# powerboard1_2.net
KiCad netlist of a schematic drawn in EAGLE
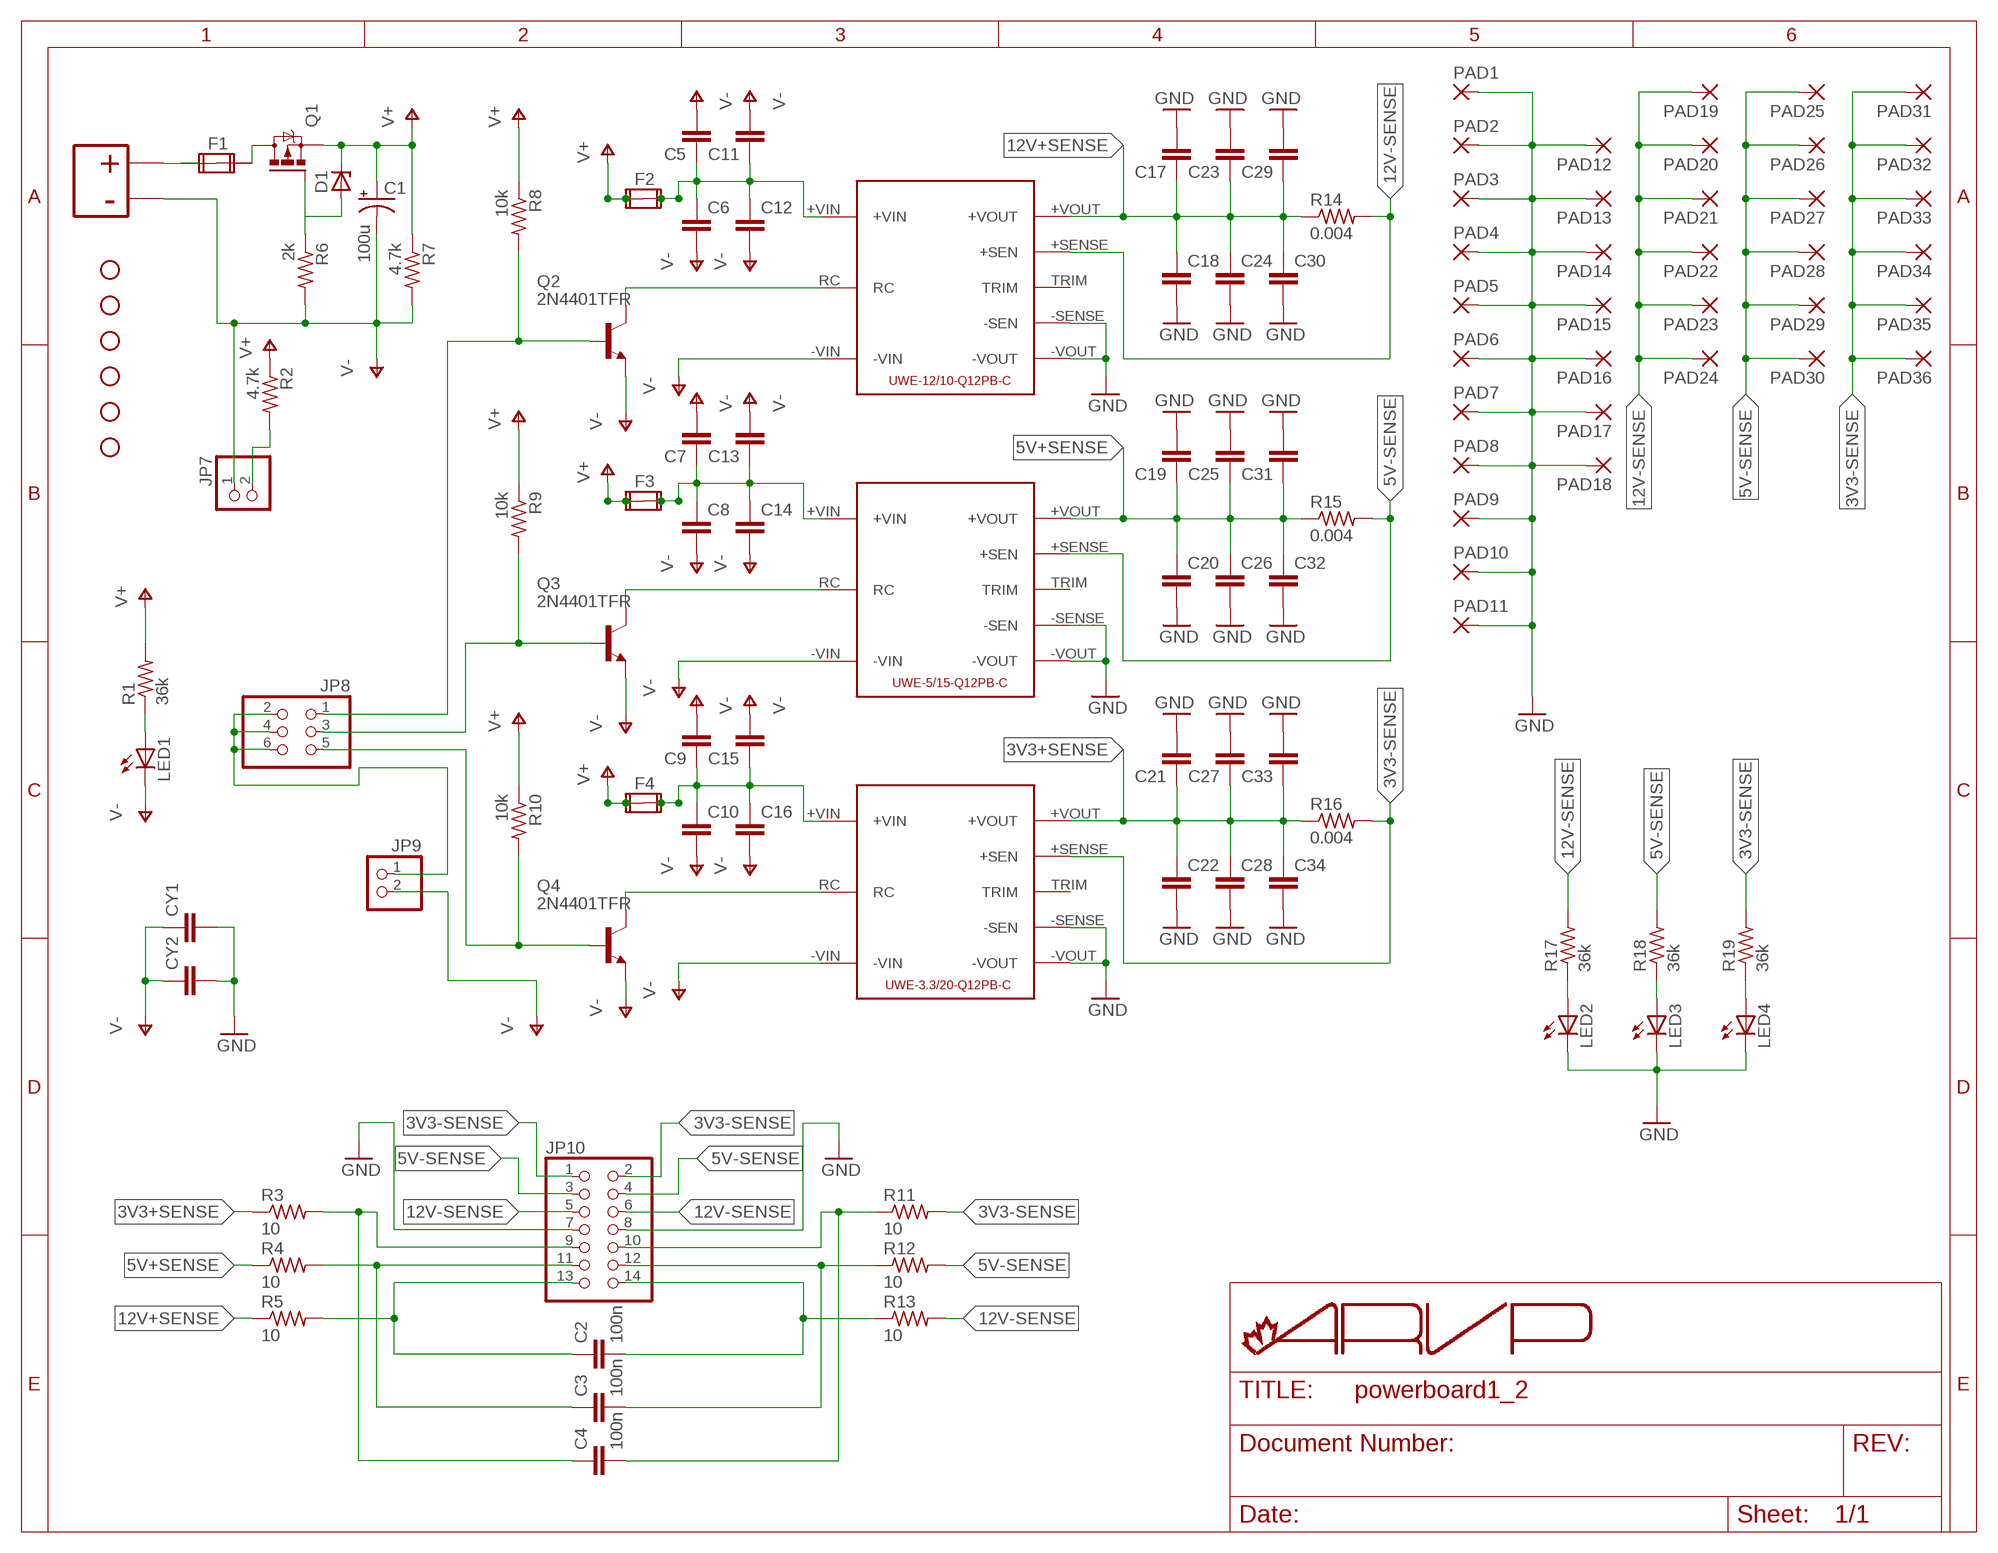
[diagram p0: schematic, sheet 1]

(export (version "E")
  (design (tool "Eeschema 10.0.6"))
  (components
    (comp (ref "C1")
      (value "100u")
      (footprint "eagle-import:E3,5-8")
      (libsource (lib "eagle-import") (part "CPOL-USE3.5-8"))
    )
    (comp (ref "C2")
      (value "100n")
      (footprint "eagle-import:C025-024X044")
      (libsource (lib "eagle-import") (part "C-EU025-024X044"))
    )
    (comp (ref "C3")
      (value "100n")
      (footprint "eagle-import:C025-024X044")
      (libsource (lib "eagle-import") (part "C-EU025-024X044"))
    )
    (comp (ref "C4")
      (value "100n")
      (footprint "eagle-import:C025-024X044")
      (libsource (lib "eagle-import") (part "C-EU025-024X044"))
    )
    (comp (ref "C5")
      (value "C-EU050-035X075")
      (footprint "eagle-import:C050-035X075")
      (libsource (lib "eagle-import") (part "C-EU050-035X075"))
    )
    (comp (ref "C6")
      (value "C-EU050-035X075")
      (footprint "eagle-import:C050-035X075")
      (libsource (lib "eagle-import") (part "C-EU050-035X075"))
    )
    (comp (ref "C7")
      (value "C-EU050-035X075")
      (footprint "eagle-import:C050-035X075")
      (libsource (lib "eagle-import") (part "C-EU050-035X075"))
    )
    (comp (ref "C8")
      (value "C-EU050-035X075")
      (footprint "eagle-import:C050-035X075")
      (libsource (lib "eagle-import") (part "C-EU050-035X075"))
    )
    (comp (ref "C9")
      (value "C-EU050-035X075")
      (footprint "eagle-import:C050-035X075")
      (libsource (lib "eagle-import") (part "C-EU050-035X075"))
    )
    (comp (ref "C10")
      (value "C-EU050-035X075")
      (footprint "eagle-import:C050-035X075")
      (libsource (lib "eagle-import") (part "C-EU050-035X075"))
    )
    (comp (ref "C11")
      (value "C-EU050-035X075")
      (footprint "eagle-import:C050-035X075")
      (libsource (lib "eagle-import") (part "C-EU050-035X075"))
    )
    (comp (ref "C12")
      (value "C-EU050-035X075")
      (footprint "eagle-import:C050-035X075")
      (libsource (lib "eagle-import") (part "C-EU050-035X075"))
    )
    (comp (ref "C13")
      (value "C-EU050-035X075")
      (footprint "eagle-import:C050-035X075")
      (libsource (lib "eagle-import") (part "C-EU050-035X075"))
    )
    (comp (ref "C14")
      (value "C-EU050-035X075")
      (footprint "eagle-import:C050-035X075")
      (libsource (lib "eagle-import") (part "C-EU050-035X075"))
    )
    (comp (ref "C15")
      (value "C-EU050-035X075")
      (footprint "eagle-import:C050-035X075")
      (libsource (lib "eagle-import") (part "C-EU050-035X075"))
    )
    (comp (ref "C16")
      (value "C-EU050-035X075")
      (footprint "eagle-import:C050-035X075")
      (libsource (lib "eagle-import") (part "C-EU050-035X075"))
    )
    (comp (ref "C17")
      (value "C-EU025-040X050")
      (footprint "eagle-import:C025-040X050")
      (libsource (lib "eagle-import") (part "C-EU025-040X050"))
    )
    (comp (ref "C18")
      (value "C-EU025-040X050")
      (footprint "eagle-import:C025-040X050")
      (libsource (lib "eagle-import") (part "C-EU025-040X050"))
    )
    (comp (ref "C19")
      (value "C-EU025-040X050")
      (footprint "eagle-import:C025-040X050")
      (libsource (lib "eagle-import") (part "C-EU025-040X050"))
    )
    (comp (ref "C20")
      (value "C-EU025-040X050")
      (footprint "eagle-import:C025-040X050")
      (libsource (lib "eagle-import") (part "C-EU025-040X050"))
    )
    (comp (ref "C21")
      (value "C-EU025-040X050")
      (footprint "eagle-import:C025-040X050")
      (libsource (lib "eagle-import") (part "C-EU025-040X050"))
    )
    (comp (ref "C22")
      (value "C-EU025-040X050")
      (footprint "eagle-import:C025-040X050")
      (libsource (lib "eagle-import") (part "C-EU025-040X050"))
    )
    (comp (ref "C23")
      (value "C-EU025-040X050")
      (footprint "eagle-import:C025-040X050")
      (libsource (lib "eagle-import") (part "C-EU025-040X050"))
    )
    (comp (ref "C24")
      (value "C-EU025-040X050")
      (footprint "eagle-import:C025-040X050")
      (libsource (lib "eagle-import") (part "C-EU025-040X050"))
    )
    (comp (ref "C25")
      (value "C-EU025-040X050")
      (footprint "eagle-import:C025-040X050")
      (libsource (lib "eagle-import") (part "C-EU025-040X050"))
    )
    (comp (ref "C26")
      (value "C-EU025-040X050")
      (footprint "eagle-import:C025-040X050")
      (libsource (lib "eagle-import") (part "C-EU025-040X050"))
    )
    (comp (ref "C27")
      (value "C-EU025-040X050")
      (footprint "eagle-import:C025-040X050")
      (libsource (lib "eagle-import") (part "C-EU025-040X050"))
    )
    (comp (ref "C28")
      (value "C-EU025-040X050")
      (footprint "eagle-import:C025-040X050")
      (libsource (lib "eagle-import") (part "C-EU025-040X050"))
    )
    (comp (ref "C29")
      (value "C-EU025-040X050")
      (footprint "eagle-import:C025-040X050")
      (libsource (lib "eagle-import") (part "C-EU025-040X050"))
    )
    (comp (ref "C30")
      (value "C-EU025-040X050")
      (footprint "eagle-import:C025-040X050")
      (libsource (lib "eagle-import") (part "C-EU025-040X050"))
    )
    (comp (ref "C31")
      (value "C-EU025-040X050")
      (footprint "eagle-import:C025-040X050")
      (libsource (lib "eagle-import") (part "C-EU025-040X050"))
    )
    (comp (ref "C32")
      (value "C-EU025-040X050")
      (footprint "eagle-import:C025-040X050")
      (libsource (lib "eagle-import") (part "C-EU025-040X050"))
    )
    (comp (ref "C33")
      (value "C-EU025-040X050")
      (footprint "eagle-import:C025-040X050")
      (libsource (lib "eagle-import") (part "C-EU025-040X050"))
    )
    (comp (ref "C34")
      (value "C-EU025-040X050")
      (footprint "eagle-import:C025-040X050")
      (libsource (lib "eagle-import") (part "C-EU025-040X050"))
    )
    (comp (ref "CY1")
      (value "CYYC7B5")
      (footprint "eagle-import:YC7B5")
      (libsource (lib "eagle-import") (part "CYYC7B5"))
    )
    (comp (ref "CY2")
      (value "CYYC7B5")
      (footprint "eagle-import:YC7B5")
      (libsource (lib "eagle-import") (part "CYYC7B5"))
    )
    (comp (ref "D1")
      (value "BZV10")
      (footprint "eagle-import:DO34Z7")
      (libsource (lib "eagle-import") (part "BZV10"))
    )
    (comp (ref "F1")
      (value "FUSE2P")
      (footprint "eagle-import:FUSE1")
      (libsource (lib "eagle-import") (part "FUSE2P"))
    )
    (comp (ref "F2")
      (value "FUSE2P")
      (footprint "eagle-import:FUSE1")
      (libsource (lib "eagle-import") (part "FUSE2P"))
    )
    (comp (ref "F3")
      (value "FUSE2P")
      (footprint "eagle-import:FUSE1")
      (libsource (lib "eagle-import") (part "FUSE2P"))
    )
    (comp (ref "F4")
      (value "FUSE2P")
      (footprint "eagle-import:FUSE1")
      (libsource (lib "eagle-import") (part "FUSE2P"))
    )
    (comp (ref "JP1")
      (value "STAND-OFF")
      (footprint "eagle-import:STAND-OFF")
      (libsource (lib "eagle-import") (part "STAND-OFF"))
    )
    (comp (ref "JP2")
      (value "STAND-OFF")
      (footprint "eagle-import:STAND-OFF")
      (libsource (lib "eagle-import") (part "STAND-OFF"))
    )
    (comp (ref "JP3")
      (value "STAND-OFF")
      (footprint "eagle-import:STAND-OFF")
      (libsource (lib "eagle-import") (part "STAND-OFF"))
    )
    (comp (ref "JP4")
      (value "STAND-OFF")
      (footprint "eagle-import:STAND-OFF")
      (libsource (lib "eagle-import") (part "STAND-OFF"))
    )
    (comp (ref "JP5")
      (value "STAND-OFF")
      (footprint "eagle-import:STAND-OFF")
      (libsource (lib "eagle-import") (part "STAND-OFF"))
    )
    (comp (ref "JP6")
      (value "STAND-OFF")
      (footprint "eagle-import:STAND-OFF")
      (libsource (lib "eagle-import") (part "STAND-OFF"))
    )
    (comp (ref "JP7")
      (value "PINHD-1X2/90")
      (footprint "eagle-import:1X02_90")
      (libsource (lib "eagle-import") (part "PINHD-1X2/90"))
    )
    (comp (ref "JP8")
      (value "PINHD-2X3/90")
      (footprint "eagle-import:2X03_90")
      (libsource (lib "eagle-import") (part "PINHD-2X3/90"))
    )
    (comp (ref "JP9")
      (value "PINHD-1X2/90")
      (footprint "eagle-import:1X02_90")
      (libsource (lib "eagle-import") (part "PINHD-1X2/90"))
    )
    (comp (ref "JP10")
      (value "PINHD-2X7")
      (footprint "eagle-import:2X07")
      (libsource (lib "eagle-import") (part "PINHD-2X7"))
    )
    (comp (ref "LED1")
      (value "LED3MM")
      (footprint "eagle-import:LED3MM")
      (libsource (lib "eagle-import") (part "LED3MM"))
    )
    (comp (ref "LED2")
      (value "LED3MM")
      (footprint "eagle-import:LED3MM")
      (libsource (lib "eagle-import") (part "LED3MM"))
    )
    (comp (ref "LED3")
      (value "LED3MM")
      (footprint "eagle-import:LED3MM")
      (libsource (lib "eagle-import") (part "LED3MM"))
    )
    (comp (ref "LED4")
      (value "LED3MM")
      (footprint "eagle-import:LED3MM")
      (libsource (lib "eagle-import") (part "LED3MM"))
    )
    (comp (ref "PAD1")
      (value "WIREPAD3,17/1,3")
      (footprint "eagle-import:3,17_1,3")
      (libsource (lib "eagle-import") (part "WIREPAD3,17/1,3"))
    )
    (comp (ref "PAD2")
      (value "WIREPAD3,17/1,3")
      (footprint "eagle-import:3,17_1,3")
      (libsource (lib "eagle-import") (part "WIREPAD3,17/1,3"))
    )
    (comp (ref "PAD3")
      (value "WIREPAD3,17/1,3")
      (footprint "eagle-import:3,17_1,3")
      (libsource (lib "eagle-import") (part "WIREPAD3,17/1,3"))
    )
    (comp (ref "PAD4")
      (value "WIREPAD3,17/1,3")
      (footprint "eagle-import:3,17_1,3")
      (libsource (lib "eagle-import") (part "WIREPAD3,17/1,3"))
    )
    (comp (ref "PAD5")
      (value "WIREPAD3,17/1,3")
      (footprint "eagle-import:3,17_1,3")
      (libsource (lib "eagle-import") (part "WIREPAD3,17/1,3"))
    )
    (comp (ref "PAD6")
      (value "WIREPAD3,17/1,3")
      (footprint "eagle-import:3,17_1,3")
      (libsource (lib "eagle-import") (part "WIREPAD3,17/1,3"))
    )
    (comp (ref "PAD7")
      (value "WIREPAD3,17/1,3")
      (footprint "eagle-import:3,17_1,3")
      (libsource (lib "eagle-import") (part "WIREPAD3,17/1,3"))
    )
    (comp (ref "PAD8")
      (value "WIREPAD3,17/1,3")
      (footprint "eagle-import:3,17_1,3")
      (libsource (lib "eagle-import") (part "WIREPAD3,17/1,3"))
    )
    (comp (ref "PAD9")
      (value "WIREPAD3,17/1,3")
      (footprint "eagle-import:3,17_1,3")
      (libsource (lib "eagle-import") (part "WIREPAD3,17/1,3"))
    )
    (comp (ref "PAD10")
      (value "WIREPAD3,17/1,3")
      (footprint "eagle-import:3,17_1,3")
      (libsource (lib "eagle-import") (part "WIREPAD3,17/1,3"))
    )
    (comp (ref "PAD11")
      (value "WIREPAD3,17/1,3")
      (footprint "eagle-import:3,17_1,3")
      (libsource (lib "eagle-import") (part "WIREPAD3,17/1,3"))
    )
    (comp (ref "PAD12")
      (value "WIREPAD3,17/1,3")
      (footprint "eagle-import:3,17_1,3")
      (libsource (lib "eagle-import") (part "WIREPAD3,17/1,3"))
    )
    (comp (ref "PAD13")
      (value "WIREPAD3,17/1,3")
      (footprint "eagle-import:3,17_1,3")
      (libsource (lib "eagle-import") (part "WIREPAD3,17/1,3"))
    )
    (comp (ref "PAD14")
      (value "WIREPAD3,17/1,3")
      (footprint "eagle-import:3,17_1,3")
      (libsource (lib "eagle-import") (part "WIREPAD3,17/1,3"))
    )
    (comp (ref "PAD15")
      (value "WIREPAD3,17/1,3")
      (footprint "eagle-import:3,17_1,3")
      (libsource (lib "eagle-import") (part "WIREPAD3,17/1,3"))
    )
    (comp (ref "PAD16")
      (value "WIREPAD3,17/1,3")
      (footprint "eagle-import:3,17_1,3")
      (libsource (lib "eagle-import") (part "WIREPAD3,17/1,3"))
    )
    (comp (ref "PAD17")
      (value "WIREPAD3,17/1,3")
      (footprint "eagle-import:3,17_1,3")
      (libsource (lib "eagle-import") (part "WIREPAD3,17/1,3"))
    )
    (comp (ref "PAD18")
      (value "WIREPAD3,17/1,3")
      (footprint "eagle-import:3,17_1,3")
      (libsource (lib "eagle-import") (part "WIREPAD3,17/1,3"))
    )
    (comp (ref "PAD19")
      (value "WIREPAD3,17/1,3")
      (footprint "eagle-import:3,17_1,3")
      (libsource (lib "eagle-import") (part "WIREPAD3,17/1,3"))
    )
    (comp (ref "PAD20")
      (value "WIREPAD3,17/1,3")
      (footprint "eagle-import:3,17_1,3")
      (libsource (lib "eagle-import") (part "WIREPAD3,17/1,3"))
    )
    (comp (ref "PAD21")
      (value "WIREPAD3,17/1,3")
      (footprint "eagle-import:3,17_1,3")
      (libsource (lib "eagle-import") (part "WIREPAD3,17/1,3"))
    )
    (comp (ref "PAD22")
      (value "WIREPAD3,17/1,3")
      (footprint "eagle-import:3,17_1,3")
      (libsource (lib "eagle-import") (part "WIREPAD3,17/1,3"))
    )
    (comp (ref "PAD23")
      (value "WIREPAD3,17/1,3")
      (footprint "eagle-import:3,17_1,3")
      (libsource (lib "eagle-import") (part "WIREPAD3,17/1,3"))
    )
    (comp (ref "PAD24")
      (value "WIREPAD3,17/1,3")
      (footprint "eagle-import:3,17_1,3")
      (libsource (lib "eagle-import") (part "WIREPAD3,17/1,3"))
    )
    (comp (ref "PAD25")
      (value "WIREPAD3,17/1,3")
      (footprint "eagle-import:3,17_1,3")
      (libsource (lib "eagle-import") (part "WIREPAD3,17/1,3"))
    )
    (comp (ref "PAD26")
      (value "WIREPAD3,17/1,3")
      (footprint "eagle-import:3,17_1,3")
      (libsource (lib "eagle-import") (part "WIREPAD3,17/1,3"))
    )
    (comp (ref "PAD27")
      (value "WIREPAD3,17/1,3")
      (footprint "eagle-import:3,17_1,3")
      (libsource (lib "eagle-import") (part "WIREPAD3,17/1,3"))
    )
    (comp (ref "PAD28")
      (value "WIREPAD3,17/1,3")
      (footprint "eagle-import:3,17_1,3")
      (libsource (lib "eagle-import") (part "WIREPAD3,17/1,3"))
    )
    (comp (ref "PAD29")
      (value "WIREPAD3,17/1,3")
      (footprint "eagle-import:3,17_1,3")
      (libsource (lib "eagle-import") (part "WIREPAD3,17/1,3"))
    )
    (comp (ref "PAD30")
      (value "WIREPAD3,17/1,3")
      (footprint "eagle-import:3,17_1,3")
      (libsource (lib "eagle-import") (part "WIREPAD3,17/1,3"))
    )
    (comp (ref "PAD31")
      (value "WIREPAD3,17/1,3")
      (footprint "eagle-import:3,17_1,3")
      (libsource (lib "eagle-import") (part "WIREPAD3,17/1,3"))
    )
    (comp (ref "PAD32")
      (value "WIREPAD3,17/1,3")
      (footprint "eagle-import:3,17_1,3")
      (libsource (lib "eagle-import") (part "WIREPAD3,17/1,3"))
    )
    (comp (ref "PAD33")
      (value "WIREPAD3,17/1,3")
      (footprint "eagle-import:3,17_1,3")
      (libsource (lib "eagle-import") (part "WIREPAD3,17/1,3"))
    )
    (comp (ref "PAD34")
      (value "WIREPAD3,17/1,3")
      (footprint "eagle-import:3,17_1,3")
      (libsource (lib "eagle-import") (part "WIREPAD3,17/1,3"))
    )
    (comp (ref "PAD35")
      (value "WIREPAD3,17/1,3")
      (footprint "eagle-import:3,17_1,3")
      (libsource (lib "eagle-import") (part "WIREPAD3,17/1,3"))
    )
    (comp (ref "PAD36")
      (value "WIREPAD3,17/1,3")
      (footprint "eagle-import:3,17_1,3")
      (libsource (lib "eagle-import") (part "WIREPAD3,17/1,3"))
    )
    (comp (ref "Q1")
      (value "IPP80P03P4L04AKSA1")
      (footprint "eagle-import:TO220BV")
      (libsource (lib "eagle-import") (part "IPP80P03P4L04AKSA1"))
    )
    (comp (ref "Q2")
      (value "2N4401TFR")
      (footprint "eagle-import:TO92-EBC")
      (libsource (lib "eagle-import") (part "2N4401TFR"))
    )
    (comp (ref "Q3")
      (value "2N4401TFR")
      (footprint "eagle-import:TO92-EBC")
      (libsource (lib "eagle-import") (part "2N4401TFR"))
    )
    (comp (ref "Q4")
      (value "2N4401TFR")
      (footprint "eagle-import:TO92-EBC")
      (libsource (lib "eagle-import") (part "2N4401TFR"))
    )
    (comp (ref "R1")
      (value "36k")
      (footprint "eagle-import:0204_7")
      (libsource (lib "eagle-import") (part "resistor_R-US_0204/7"))
    )
    (comp (ref "R2")
      (value "4.7k")
      (footprint "eagle-import:0204_7")
      (libsource (lib "eagle-import") (part "resistor_R-US_0204/7"))
    )
    (comp (ref "R3")
      (value "10")
      (footprint "eagle-import:0204_5")
      (libsource (lib "eagle-import") (part "R-US_0204/5"))
    )
    (comp (ref "R4")
      (value "10")
      (footprint "eagle-import:0204_5")
      (libsource (lib "eagle-import") (part "R-US_0204/5"))
    )
    (comp (ref "R5")
      (value "10")
      (footprint "eagle-import:0204_5")
      (libsource (lib "eagle-import") (part "R-US_0204/5"))
    )
    (comp (ref "R6")
      (value "2k")
      (footprint "eagle-import:0204_7")
      (libsource (lib "eagle-import") (part "resistor_R-US_0204/7"))
    )
    (comp (ref "R7")
      (value "4.7k")
      (footprint "eagle-import:0204_7")
      (libsource (lib "eagle-import") (part "resistor_R-US_0204/7"))
    )
    (comp (ref "R8")
      (value "10k")
      (footprint "eagle-import:0204_7")
      (libsource (lib "eagle-import") (part "resistor_R-US_0204/7"))
    )
    (comp (ref "R9")
      (value "10k")
      (footprint "eagle-import:0204_7")
      (libsource (lib "eagle-import") (part "resistor_R-US_0204/7"))
    )
    (comp (ref "R10")
      (value "10k")
      (footprint "eagle-import:0204_7")
      (libsource (lib "eagle-import") (part "resistor_R-US_0204/7"))
    )
    (comp (ref "R11")
      (value "10")
      (footprint "eagle-import:0204_5")
      (libsource (lib "eagle-import") (part "R-US_0204/5"))
    )
    (comp (ref "R12")
      (value "10")
      (footprint "eagle-import:0204_5")
      (libsource (lib "eagle-import") (part "R-US_0204/5"))
    )
    (comp (ref "R13")
      (value "10")
      (footprint "eagle-import:0204_5")
      (libsource (lib "eagle-import") (part "R-US_0204/5"))
    )
    (comp (ref "R14")
      (value "0.004")
      (footprint "eagle-import:0617_22")
      (libsource (lib "eagle-import") (part "R-US_0617/22"))
    )
    (comp (ref "R15")
      (value "0.004")
      (footprint "eagle-import:0617_22")
      (libsource (lib "eagle-import") (part "R-US_0617/22"))
    )
    (comp (ref "R16")
      (value "0.004")
      (footprint "eagle-import:0617_22")
      (libsource (lib "eagle-import") (part "R-US_0617/22"))
    )
    (comp (ref "R17")
      (value "36k")
      (footprint "eagle-import:0204_7")
      (libsource (lib "eagle-import") (part "resistor_R-US_0204/7"))
    )
    (comp (ref "R18")
      (value "36k")
      (footprint "eagle-import:0204_7")
      (libsource (lib "eagle-import") (part "resistor_R-US_0204/7"))
    )
    (comp (ref "R19")
      (value "36k")
      (footprint "eagle-import:0204_7")
      (libsource (lib "eagle-import") (part "resistor_R-US_0204/7"))
    )
    (comp (ref "T1")
      (value "2_POS_TERMINAL")
      (footprint "eagle-import:PHOENIX_CONTACT_MKDS_5_2-7.62")
      (libsource (lib "eagle-import") (part "2_POS_TERMINAL"))
    )
    (comp (ref "U1")
      (value "UWE-12/10-Q12PB-C")
      (footprint "eagle-import:UWE-100-120W")
      (libsource (lib "eagle-import") (part "UWE-12/10-Q12PB-C"))
    )
    (comp (ref "U2")
      (value "UWE-5/15-Q12PB-C")
      (footprint "eagle-import:UWE-100-120W")
      (libsource (lib "eagle-import") (part "UWE-5/15-Q12PB-C"))
    )
    (comp (ref "U3")
      (value "UWE-3.3/20-Q12PB-C")
      (footprint "eagle-import:UWE-100-120W")
      (libsource (lib "eagle-import") (part "UWE-3.3/20-Q12PB-C"))
    )
  )
  (nets
    (net (code "1") (name "3V3+SENSE") (class "Default")
      (node (ref "C21") (pin "1") (pinfunction "1_1") (pintype "passive"))
      (node (ref "C22") (pin "1") (pinfunction "1_1") (pintype "passive"))
      (node (ref "C27") (pin "1") (pinfunction "1_1") (pintype "passive"))
      (node (ref "C28") (pin "1") (pinfunction "1_1") (pintype "passive"))
      (node (ref "C33") (pin "1") (pinfunction "1_1") (pintype "passive"))
      (node (ref "C34") (pin "1") (pinfunction "1_1") (pintype "passive"))
      (node (ref "R16") (pin "1") (pinfunction "1_1") (pintype "passive"))
      (node (ref "R3") (pin "1") (pinfunction "1_1") (pintype "passive"))
      (node (ref "U3") (pin "+VOUT") (pinfunction "+VOUT_+VOUT") (pintype "power_in"))
    )
    (net (code "2") (name "3V3-SENSE") (class "Default")
      (node (ref "JP10") (pin "1") (pinfunction "1_1") (pintype "passive"))
      (node (ref "JP10") (pin "2") (pinfunction "2_2") (pintype "passive"))
      (node (ref "PAD31") (pin "1") (pinfunction "P_1") (pintype "passive"))
      (node (ref "PAD32") (pin "1") (pinfunction "P_1") (pintype "passive"))
      (node (ref "PAD33") (pin "1") (pinfunction "P_1") (pintype "passive"))
      (node (ref "PAD34") (pin "1") (pinfunction "P_1") (pintype "passive"))
      (node (ref "PAD35") (pin "1") (pinfunction "P_1") (pintype "passive"))
      (node (ref "PAD36") (pin "1") (pinfunction "P_1") (pintype "passive"))
      (node (ref "R11") (pin "2") (pinfunction "2_2") (pintype "passive"))
      (node (ref "R16") (pin "2") (pinfunction "2_2") (pintype "passive"))
      (node (ref "R19") (pin "2") (pinfunction "2_2") (pintype "passive"))
      (node (ref "U3") (pin "+SENSE") (pinfunction "+SEN_+SENSE") (pintype "bidirectional"))
    )
    (net (code "3") (name "5V+SENSE") (class "Default")
      (node (ref "C19") (pin "1") (pinfunction "1_1") (pintype "passive"))
      (node (ref "C20") (pin "1") (pinfunction "1_1") (pintype "passive"))
      (node (ref "C25") (pin "1") (pinfunction "1_1") (pintype "passive"))
      (node (ref "C26") (pin "1") (pinfunction "1_1") (pintype "passive"))
      (node (ref "C31") (pin "1") (pinfunction "1_1") (pintype "passive"))
      (node (ref "C32") (pin "1") (pinfunction "1_1") (pintype "passive"))
      (node (ref "R15") (pin "1") (pinfunction "1_1") (pintype "passive"))
      (node (ref "R4") (pin "1") (pinfunction "1_1") (pintype "passive"))
      (node (ref "U2") (pin "+VOUT") (pinfunction "+VOUT_+VOUT") (pintype "power_in"))
    )
    (net (code "4") (name "5V-SENSE") (class "Default")
      (node (ref "JP10") (pin "3") (pinfunction "3_3") (pintype "passive"))
      (node (ref "JP10") (pin "4") (pinfunction "4_4") (pintype "passive"))
      (node (ref "PAD25") (pin "1") (pinfunction "P_1") (pintype "passive"))
      (node (ref "PAD26") (pin "1") (pinfunction "P_1") (pintype "passive"))
      (node (ref "PAD27") (pin "1") (pinfunction "P_1") (pintype "passive"))
      (node (ref "PAD28") (pin "1") (pinfunction "P_1") (pintype "passive"))
      (node (ref "PAD29") (pin "1") (pinfunction "P_1") (pintype "passive"))
      (node (ref "PAD30") (pin "1") (pinfunction "P_1") (pintype "passive"))
      (node (ref "R12") (pin "2") (pinfunction "2_2") (pintype "passive"))
      (node (ref "R15") (pin "2") (pinfunction "2_2") (pintype "passive"))
      (node (ref "R18") (pin "2") (pinfunction "2_2") (pintype "passive"))
      (node (ref "U2") (pin "+SENSE") (pinfunction "+SEN_+SENSE") (pintype "bidirectional"))
    )
    (net (code "5") (name "12V+SENSE") (class "Default")
      (node (ref "C17") (pin "1") (pinfunction "1_1") (pintype "passive"))
      (node (ref "C18") (pin "1") (pinfunction "1_1") (pintype "passive"))
      (node (ref "C23") (pin "1") (pinfunction "1_1") (pintype "passive"))
      (node (ref "C24") (pin "1") (pinfunction "1_1") (pintype "passive"))
      (node (ref "C29") (pin "1") (pinfunction "1_1") (pintype "passive"))
      (node (ref "C30") (pin "1") (pinfunction "1_1") (pintype "passive"))
      (node (ref "R14") (pin "1") (pinfunction "1_1") (pintype "passive"))
      (node (ref "R5") (pin "1") (pinfunction "1_1") (pintype "passive"))
      (node (ref "U1") (pin "+VOUT") (pinfunction "+VOUT_+VOUT") (pintype "power_in"))
    )
    (net (code "6") (name "12V-SENSE") (class "Default")
      (node (ref "JP10") (pin "5") (pinfunction "5_5") (pintype "passive"))
      (node (ref "JP10") (pin "6") (pinfunction "6_6") (pintype "passive"))
      (node (ref "PAD19") (pin "1") (pinfunction "P_1") (pintype "passive"))
      (node (ref "PAD20") (pin "1") (pinfunction "P_1") (pintype "passive"))
      (node (ref "PAD21") (pin "1") (pinfunction "P_1") (pintype "passive"))
      (node (ref "PAD22") (pin "1") (pinfunction "P_1") (pintype "passive"))
      (node (ref "PAD23") (pin "1") (pinfunction "P_1") (pintype "passive"))
      (node (ref "PAD24") (pin "1") (pinfunction "P_1") (pintype "passive"))
      (node (ref "R13") (pin "2") (pinfunction "2_2") (pintype "passive"))
      (node (ref "R14") (pin "2") (pinfunction "2_2") (pintype "passive"))
      (node (ref "R17") (pin "2") (pinfunction "2_2") (pintype "passive"))
      (node (ref "U1") (pin "+SENSE") (pinfunction "+SEN_+SENSE") (pintype "bidirectional"))
    )
    (net (code "7") (name "GND") (class "Default")
      (node (ref "C17") (pin "2") (pinfunction "2_2") (pintype "passive"))
      (node (ref "C18") (pin "2") (pinfunction "2_2") (pintype "passive"))
      (node (ref "C19") (pin "2") (pinfunction "2_2") (pintype "passive"))
      (node (ref "C20") (pin "2") (pinfunction "2_2") (pintype "passive"))
      (node (ref "C21") (pin "2") (pinfunction "2_2") (pintype "passive"))
      (node (ref "C22") (pin "2") (pinfunction "2_2") (pintype "passive"))
      (node (ref "C23") (pin "2") (pinfunction "2_2") (pintype "passive"))
      (node (ref "C24") (pin "2") (pinfunction "2_2") (pintype "passive"))
      (node (ref "C25") (pin "2") (pinfunction "2_2") (pintype "passive"))
      (node (ref "C26") (pin "2") (pinfunction "2_2") (pintype "passive"))
      (node (ref "C27") (pin "2") (pinfunction "2_2") (pintype "passive"))
      (node (ref "C28") (pin "2") (pinfunction "2_2") (pintype "passive"))
      (node (ref "C29") (pin "2") (pinfunction "2_2") (pintype "passive"))
      (node (ref "C30") (pin "2") (pinfunction "2_2") (pintype "passive"))
      (node (ref "C31") (pin "2") (pinfunction "2_2") (pintype "passive"))
      (node (ref "C32") (pin "2") (pinfunction "2_2") (pintype "passive"))
      (node (ref "C33") (pin "2") (pinfunction "2_2") (pintype "passive"))
      (node (ref "C34") (pin "2") (pinfunction "2_2") (pintype "passive"))
      (node (ref "CY1") (pin "2") (pinfunction "2_2") (pintype "passive"))
      (node (ref "CY2") (pin "2") (pinfunction "2_2") (pintype "passive"))
      (node (ref "JP10") (pin "7") (pinfunction "7_7") (pintype "passive"))
      (node (ref "JP10") (pin "8") (pinfunction "8_8") (pintype "passive"))
      (node (ref "LED2") (pin "K") (pinfunction "C_K") (pintype "passive"))
      (node (ref "LED3") (pin "K") (pinfunction "C_K") (pintype "passive"))
      (node (ref "LED4") (pin "K") (pinfunction "C_K") (pintype "passive"))
      (node (ref "PAD1") (pin "1") (pinfunction "P_1") (pintype "passive"))
      (node (ref "PAD10") (pin "1") (pinfunction "P_1") (pintype "passive"))
      (node (ref "PAD11") (pin "1") (pinfunction "P_1") (pintype "passive"))
      (node (ref "PAD12") (pin "1") (pinfunction "P_1") (pintype "passive"))
      (node (ref "PAD13") (pin "1") (pinfunction "P_1") (pintype "passive"))
      (node (ref "PAD14") (pin "1") (pinfunction "P_1") (pintype "passive"))
      (node (ref "PAD15") (pin "1") (pinfunction "P_1") (pintype "passive"))
      (node (ref "PAD16") (pin "1") (pinfunction "P_1") (pintype "passive"))
      (node (ref "PAD17") (pin "1") (pinfunction "P_1") (pintype "passive"))
      (node (ref "PAD18") (pin "1") (pinfunction "P_1") (pintype "passive"))
      (node (ref "PAD2") (pin "1") (pinfunction "P_1") (pintype "passive"))
      (node (ref "PAD3") (pin "1") (pinfunction "P_1") (pintype "passive"))
      (node (ref "PAD4") (pin "1") (pinfunction "P_1") (pintype "passive"))
      (node (ref "PAD5") (pin "1") (pinfunction "P_1") (pintype "passive"))
      (node (ref "PAD6") (pin "1") (pinfunction "P_1") (pintype "passive"))
      (node (ref "PAD7") (pin "1") (pinfunction "P_1") (pintype "passive"))
      (node (ref "PAD8") (pin "1") (pinfunction "P_1") (pintype "passive"))
      (node (ref "PAD9") (pin "1") (pinfunction "P_1") (pintype "passive"))
      (node (ref "U1") (pin "-SENSE") (pinfunction "-SEN_-SENSE") (pintype "bidirectional"))
      (node (ref "U1") (pin "-VOUT") (pinfunction "-VOUT_-VOUT") (pintype "power_in"))
      (node (ref "U2") (pin "-SENSE") (pinfunction "-SEN_-SENSE") (pintype "bidirectional"))
      (node (ref "U2") (pin "-VOUT") (pinfunction "-VOUT_-VOUT") (pintype "power_in"))
      (node (ref "U3") (pin "-SENSE") (pinfunction "-SEN_-SENSE") (pintype "bidirectional"))
      (node (ref "U3") (pin "-VOUT") (pinfunction "-VOUT_-VOUT") (pintype "power_in"))
    )
    (net (code "8") (name "Net-(C2-Pad1)") (class "Default")
      (node (ref "C2") (pin "1") (pinfunction "1_1") (pintype "passive"))
      (node (ref "JP10") (pin "13") (pinfunction "13_13") (pintype "passive"))
      (node (ref "R5") (pin "2") (pinfunction "2_2") (pintype "passive"))
    )
    (net (code "9") (name "Net-(C2-Pad2)") (class "Default")
      (node (ref "C2") (pin "2") (pinfunction "2_2") (pintype "passive"))
      (node (ref "JP10") (pin "14") (pinfunction "14_14") (pintype "passive"))
      (node (ref "R13") (pin "1") (pinfunction "1_1") (pintype "passive"))
    )
    (net (code "10") (name "Net-(C3-Pad1)") (class "Default")
      (node (ref "C3") (pin "1") (pinfunction "1_1") (pintype "passive"))
      (node (ref "JP10") (pin "11") (pinfunction "11_11") (pintype "passive"))
      (node (ref "R4") (pin "2") (pinfunction "2_2") (pintype "passive"))
    )
    (net (code "11") (name "Net-(C3-Pad2)") (class "Default")
      (node (ref "C3") (pin "2") (pinfunction "2_2") (pintype "passive"))
      (node (ref "JP10") (pin "12") (pinfunction "12_12") (pintype "passive"))
      (node (ref "R12") (pin "1") (pinfunction "1_1") (pintype "passive"))
    )
    (net (code "12") (name "Net-(C4-Pad1)") (class "Default")
      (node (ref "C4") (pin "1") (pinfunction "1_1") (pintype "passive"))
      (node (ref "JP10") (pin "9") (pinfunction "9_9") (pintype "passive"))
      (node (ref "R3") (pin "2") (pinfunction "2_2") (pintype "passive"))
    )
    (net (code "13") (name "Net-(C4-Pad2)") (class "Default")
      (node (ref "C4") (pin "2") (pinfunction "2_2") (pintype "passive"))
      (node (ref "JP10") (pin "10") (pinfunction "10_10") (pintype "passive"))
      (node (ref "R11") (pin "1") (pinfunction "1_1") (pintype "passive"))
    )
    (net (code "14") (name "Net-(C10-Pad1)") (class "Default")
      (node (ref "C10") (pin "1") (pinfunction "1_1") (pintype "passive"))
      (node (ref "C15") (pin "1") (pinfunction "1_1") (pintype "passive"))
      (node (ref "C16") (pin "1") (pinfunction "1_1") (pintype "passive"))
      (node (ref "C9") (pin "1") (pinfunction "1_1") (pintype "passive"))
      (node (ref "F4") (pin "2A") (pinfunction "2A_2A") (pintype "passive"))
      (node (ref "F4") (pin "2B") (pinfunction "2B_2B") (pintype "passive"))
      (node (ref "U3") (pin "+VIN") (pinfunction "+VIN_+VIN") (pintype "power_in"))
    )
    (net (code "15") (name "Net-(C11-Pad1)") (class "Default")
      (node (ref "C11") (pin "1") (pinfunction "1_1") (pintype "passive"))
      (node (ref "C12") (pin "1") (pinfunction "1_1") (pintype "passive"))
      (node (ref "C5") (pin "1") (pinfunction "1_1") (pintype "passive"))
      (node (ref "C6") (pin "1") (pinfunction "1_1") (pintype "passive"))
      (node (ref "F2") (pin "2A") (pinfunction "2A_2A") (pintype "passive"))
      (node (ref "F2") (pin "2B") (pinfunction "2B_2B") (pintype "passive"))
      (node (ref "U1") (pin "+VIN") (pinfunction "+VIN_+VIN") (pintype "power_in"))
    )
    (net (code "16") (name "Net-(C13-Pad1)") (class "Default")
      (node (ref "C13") (pin "1") (pinfunction "1_1") (pintype "passive"))
      (node (ref "C14") (pin "1") (pinfunction "1_1") (pintype "passive"))
      (node (ref "C7") (pin "1") (pinfunction "1_1") (pintype "passive"))
      (node (ref "C8") (pin "1") (pinfunction "1_1") (pintype "passive"))
      (node (ref "F3") (pin "2A") (pinfunction "2A_2A") (pintype "passive"))
      (node (ref "F3") (pin "2B") (pinfunction "2B_2B") (pintype "passive"))
      (node (ref "U2") (pin "+VIN") (pinfunction "+VIN_+VIN") (pintype "power_in"))
    )
    (net (code "17") (name "Net-(D1-PadA)") (class "Default")
      (node (ref "D1") (pin "A") (pinfunction "A_A") (pintype "passive"))
      (node (ref "Q1") (pin "G") (pinfunction "G_G") (pintype "power_in"))
      (node (ref "R6") (pin "1") (pinfunction "1_1") (pintype "passive"))
    )
    (net (code "18") (name "Net-(F1-Pad1A)") (class "Default")
      (node (ref "F1") (pin "1A") (pinfunction "1A_1A") (pintype "passive"))
      (node (ref "F1") (pin "1B") (pinfunction "1B_1B") (pintype "passive"))
      (node (ref "T1") (pin "P$1") (pinfunction "P$1_P$1") (pintype "power_in"))
    )
    (net (code "19") (name "Net-(F1-Pad2A)") (class "Default")
      (node (ref "F1") (pin "2A") (pinfunction "2A_2A") (pintype "passive"))
      (node (ref "F1") (pin "2B") (pinfunction "2B_2B") (pintype "passive"))
      (node (ref "Q1") (pin "D") (pinfunction "D_D") (pintype "power_in"))
    )
    (net (code "20") (name "Net-(JP7-Pad2)") (class "Default")
      (node (ref "JP7") (pin "2") (pinfunction "2_2") (pintype "passive"))
      (node (ref "R2") (pin "2") (pinfunction "2_2") (pintype "passive"))
    )
    (net (code "21") (name "Net-(JP8-Pad1)") (class "Default")
      (node (ref "JP8") (pin "1") (pinfunction "1_1") (pintype "passive"))
      (node (ref "Q2") (pin "B") (pinfunction "B_B") (pintype "passive"))
      (node (ref "R8") (pin "2") (pinfunction "2_2") (pintype "passive"))
    )
    (net (code "22") (name "Net-(JP8-Pad2)") (class "Default")
      (node (ref "JP8") (pin "2") (pinfunction "2_2") (pintype "passive"))
      (node (ref "JP8") (pin "4") (pinfunction "4_4") (pintype "passive"))
      (node (ref "JP8") (pin "6") (pinfunction "6_6") (pintype "passive"))
      (node (ref "JP9") (pin "1") (pinfunction "1_1") (pintype "passive"))
    )
    (net (code "23") (name "Net-(JP8-Pad3)") (class "Default")
      (node (ref "JP8") (pin "3") (pinfunction "3_3") (pintype "passive"))
      (node (ref "Q3") (pin "B") (pinfunction "B_B") (pintype "passive"))
      (node (ref "R9") (pin "2") (pinfunction "2_2") (pintype "passive"))
    )
    (net (code "24") (name "Net-(JP8-Pad5)") (class "Default")
      (node (ref "JP8") (pin "5") (pinfunction "5_5") (pintype "passive"))
      (node (ref "Q4") (pin "B") (pinfunction "B_B") (pintype "passive"))
      (node (ref "R10") (pin "2") (pinfunction "2_2") (pintype "passive"))
    )
    (net (code "25") (name "Net-(LED1-PadA)") (class "Default")
      (node (ref "LED1") (pin "A") (pinfunction "A_A") (pintype "passive"))
      (node (ref "R1") (pin "1") (pinfunction "1_1") (pintype "passive"))
    )
    (net (code "26") (name "Net-(LED2-PadA)") (class "Default")
      (node (ref "LED2") (pin "A") (pinfunction "A_A") (pintype "passive"))
      (node (ref "R17") (pin "1") (pinfunction "1_1") (pintype "passive"))
    )
    (net (code "27") (name "Net-(LED3-PadA)") (class "Default")
      (node (ref "LED3") (pin "A") (pinfunction "A_A") (pintype "passive"))
      (node (ref "R18") (pin "1") (pinfunction "1_1") (pintype "passive"))
    )
    (net (code "28") (name "Net-(LED4-PadA)") (class "Default")
      (node (ref "LED4") (pin "A") (pinfunction "A_A") (pintype "passive"))
      (node (ref "R19") (pin "1") (pinfunction "1_1") (pintype "passive"))
    )
    (net (code "29") (name "Net-(Q2-PadC)") (class "Default")
      (node (ref "Q2") (pin "C") (pinfunction "C_C") (pintype "passive"))
      (node (ref "U1") (pin "RC") (pinfunction "RC_RC") (pintype "bidirectional"))
    )
    (net (code "30") (name "Net-(Q3-PadC)") (class "Default")
      (node (ref "Q3") (pin "C") (pinfunction "C_C") (pintype "passive"))
      (node (ref "U2") (pin "RC") (pinfunction "RC_RC") (pintype "bidirectional"))
    )
    (net (code "31") (name "Net-(Q4-PadC)") (class "Default")
      (node (ref "Q4") (pin "C") (pinfunction "C_C") (pintype "passive"))
      (node (ref "U3") (pin "RC") (pinfunction "RC_RC") (pintype "bidirectional"))
    )
    (net (code "32") (name "V+") (class "Default")
      (node (ref "C1") (pin "+") (pinfunction "+_+") (pintype "passive"))
      (node (ref "D1") (pin "C") (pinfunction "C_C") (pintype "passive"))
      (node (ref "F2") (pin "1A") (pinfunction "1A_1A") (pintype "passive"))
      (node (ref "F2") (pin "1B") (pinfunction "1B_1B") (pintype "passive"))
      (node (ref "F3") (pin "1A") (pinfunction "1A_1A") (pintype "passive"))
      (node (ref "F3") (pin "1B") (pinfunction "1B_1B") (pintype "passive"))
      (node (ref "F4") (pin "1A") (pinfunction "1A_1A") (pintype "passive"))
      (node (ref "F4") (pin "1B") (pinfunction "1B_1B") (pintype "passive"))
      (node (ref "Q1") (pin "S") (pinfunction "S_S") (pintype "power_in"))
      (node (ref "R1") (pin "2") (pinfunction "2_2") (pintype "passive"))
      (node (ref "R10") (pin "1") (pinfunction "1_1") (pintype "passive"))
      (node (ref "R2") (pin "1") (pinfunction "1_1") (pintype "passive"))
      (node (ref "R7") (pin "1") (pinfunction "1_1") (pintype "passive"))
      (node (ref "R8") (pin "1") (pinfunction "1_1") (pintype "passive"))
      (node (ref "R9") (pin "1") (pinfunction "1_1") (pintype "passive"))
    )
    (net (code "33") (name "V-") (class "Default")
      (node (ref "C1") (pin "-") (pinfunction "-_-") (pintype "passive"))
      (node (ref "C10") (pin "2") (pinfunction "2_2") (pintype "passive"))
      (node (ref "C11") (pin "2") (pinfunction "2_2") (pintype "passive"))
      (node (ref "C12") (pin "2") (pinfunction "2_2") (pintype "passive"))
      (node (ref "C13") (pin "2") (pinfunction "2_2") (pintype "passive"))
      (node (ref "C14") (pin "2") (pinfunction "2_2") (pintype "passive"))
      (node (ref "C15") (pin "2") (pinfunction "2_2") (pintype "passive"))
      (node (ref "C16") (pin "2") (pinfunction "2_2") (pintype "passive"))
      (node (ref "C5") (pin "2") (pinfunction "2_2") (pintype "passive"))
      (node (ref "C6") (pin "2") (pinfunction "2_2") (pintype "passive"))
      (node (ref "C7") (pin "2") (pinfunction "2_2") (pintype "passive"))
      (node (ref "C8") (pin "2") (pinfunction "2_2") (pintype "passive"))
      (node (ref "C9") (pin "2") (pinfunction "2_2") (pintype "passive"))
      (node (ref "CY1") (pin "1") (pinfunction "1_1") (pintype "passive"))
      (node (ref "CY2") (pin "1") (pinfunction "1_1") (pintype "passive"))
      (node (ref "JP7") (pin "1") (pinfunction "1_1") (pintype "passive"))
      (node (ref "JP9") (pin "2") (pinfunction "2_2") (pintype "passive"))
      (node (ref "LED1") (pin "K") (pinfunction "C_K") (pintype "passive"))
      (node (ref "Q2") (pin "E") (pinfunction "E_E") (pintype "passive"))
      (node (ref "Q3") (pin "E") (pinfunction "E_E") (pintype "passive"))
      (node (ref "Q4") (pin "E") (pinfunction "E_E") (pintype "passive"))
      (node (ref "R6") (pin "2") (pinfunction "2_2") (pintype "passive"))
      (node (ref "R7") (pin "2") (pinfunction "2_2") (pintype "passive"))
      (node (ref "T1") (pin "P$2") (pinfunction "P$2_P$2") (pintype "power_in"))
      (node (ref "U1") (pin "-VIN") (pinfunction "-VIN_-VIN") (pintype "power_in"))
      (node (ref "U2") (pin "-VIN") (pinfunction "-VIN_-VIN") (pintype "power_in"))
      (node (ref "U3") (pin "-VIN") (pinfunction "-VIN_-VIN") (pintype "power_in"))
    )
    (net (code "34") (name "unconnected-(U1-PadTRIM)") (class "Default")
      (node (ref "U1") (pin "TRIM") (pinfunction "TRIM_TRIM") (pintype "bidirectional"))
    )
    (net (code "35") (name "unconnected-(U2-PadTRIM)") (class "Default")
      (node (ref "U2") (pin "TRIM") (pinfunction "TRIM_TRIM") (pintype "bidirectional"))
    )
    (net (code "36") (name "unconnected-(U3-PadTRIM)") (class "Default")
      (node (ref "U3") (pin "TRIM") (pinfunction "TRIM_TRIM") (pintype "bidirectional"))
    )
  )
)
